# IO.net
KiCad netlist of a schematic drawn in Altium Designer
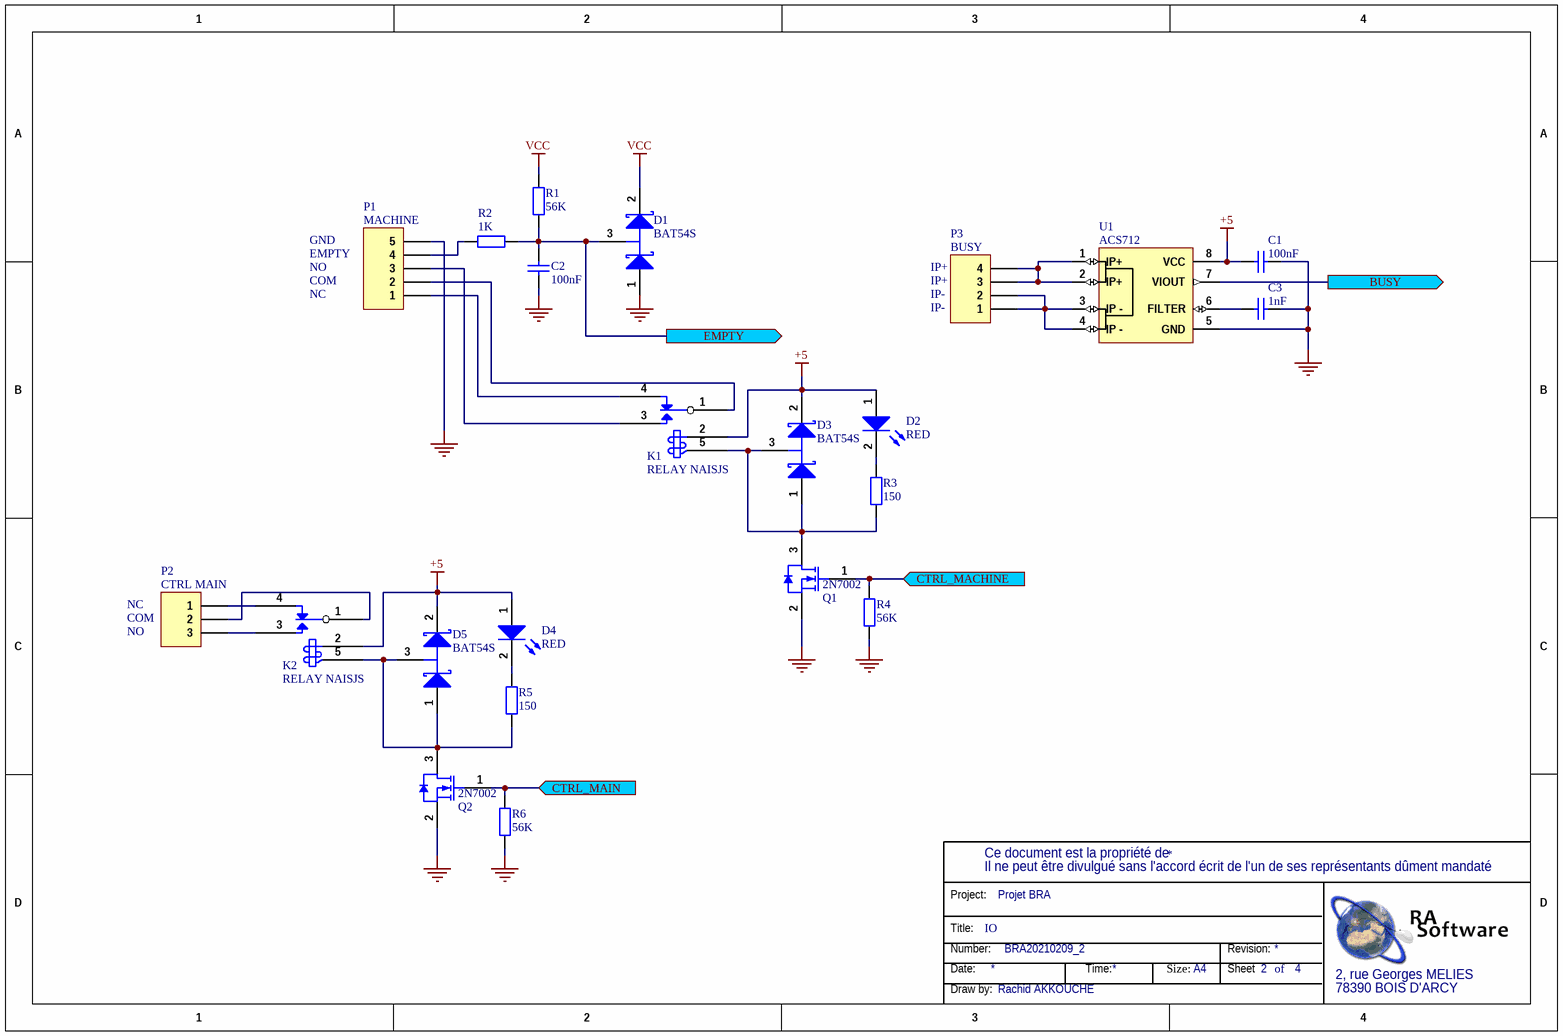
[diagram p0: IO.SchDoc]

(export (version "E")
  (design (tool "Eeschema 10.0.6"))
  (components
    (comp (ref "C1")
      (value "100nF")
      (footprint "C 0805(2012)x0.65")
      (description "Capacitor")
      (fields
        (field (name "MANUFACTURER") "MULTICOMP")
        (field (name "MANUFACTURER PART NUMBER") "MCCA000296")
      )
      (libsource (lib "BRA") (part "Cap 0805 100nF"))
    )
    (comp (ref "C2")
      (value "100nF")
      (footprint "C 0805(2012)x0.65")
      (description "Capacitor")
      (fields
        (field (name "MANUFACTURER") "MULTICOMP")
        (field (name "MANUFACTURER PART NUMBER") "MCCA000296")
      )
      (libsource (lib "BRA") (part "Cap 0805 100nF"))
    )
    (comp (ref "C3")
      (value "1nF")
      (footprint "C 0805(2012)x0.65")
      (description "Capacitor")
      (fields
        (field (name "MANUFACTURER") "SAMSUNG")
        (field (name "MANUFACTURER PART NUMBER") "CL05B102KB5NNNC")
      )
      (libsource (lib "BRA") (part "Cap 0805 1nF"))
    )
    (comp (ref "D1")
      (value "BAT54S")
      (footprint "BRA:SOT23")
      (description "Schottky Barrier Double Diode")
      (fields (field (name "MANUFACTURER") "MULTICOMP"))
      (libsource (lib "BRA") (part "BAT54S"))
    )
    (comp (ref "D2")
      (value "RED")
      (footprint "0603-LEDR")
      (description "Surface Mount Chip LED, Red")
      (fields
        (field (name "MANUFACTURER") "AVAGO TECHNOLOGIES")
        (field (name "MANUFACTURER PART NUMBER") "HSMH-C190.")
        (field (name "LONGUEUR/HAUTEUR") "1.6")
      )
      (libsource (lib "BRA") (part "HSMH-C190"))
    )
    (comp (ref "D3")
      (value "BAT54S")
      (footprint "SOT23")
      (description "Schottky Barrier Double Diode")
      (fields (field (name "MANUFACTURER") "MULTICOMP"))
      (libsource (lib "Ares") (part "BAT54S"))
    )
    (comp (ref "D4")
      (value "RED")
      (footprint "0603-LEDR")
      (description "Surface Mount Chip LED, Red")
      (fields
        (field (name "MANUFACTURER") "AVAGO TECHNOLOGIES")
        (field (name "MANUFACTURER PART NUMBER") "HSMH-C190.")
        (field (name "LONGUEUR/HAUTEUR") "1.6")
      )
      (libsource (lib "BRA") (part "HSMH-C190"))
    )
    (comp (ref "D5")
      (value "BAT54S")
      (footprint "SOT23")
      (description "Schottky Barrier Double Diode")
      (fields (field (name "MANUFACTURER") "MULTICOMP"))
      (libsource (lib "Ares") (part "BAT54S"))
    )
    (comp (ref "K1")
      (value "RELAY NAISJS")
      (footprint "RELAIG5L")
      (fields
        (field (name "MANUFACTURER") "OMRON ELECTRONIC COMPONENTS")
        (field (name "MANUFACTURER PART NUMBER") "G5LA1A412DC")
        (field (name "HAUTEUR, DIMENSION EXTERNE") "15.8")
      )
      (libsource (lib "UTIL_Library") (part "RELAY NAISJS"))
    )
    (comp (ref "K2")
      (value "RELAY NAISJS")
      (footprint "RELAIG5L")
      (fields
        (field (name "MANUFACTURER") "OMRON ELECTRONIC COMPONENTS")
        (field (name "MANUFACTURER PART NUMBER") "G5LA1A412DC")
        (field (name "HAUTEUR, DIMENSION EXTERNE") "15.8")
      )
      (libsource (lib "UTIL_Library") (part "RELAY NAISJS"))
    )
    (comp (ref "P1")
      (value "MACHINE")
      (footprint "CO5P508-RIGHT")
      (description "Header, 5-Pin")
      (fields (field (name "PUBLISHER") "Altium Limited"))
      (libsource (lib "Miscellaneous Connectors") (part "Header 5"))
    )
    (comp (ref "P2")
      (value "CTRL MAIN")
      (footprint "CO3P508 - 2")
      (description "Header, 3-Pin")
      (fields (field (name "PUBLISHER") "Altium Limited"))
      (libsource (lib "Miscellaneous Connectors") (part "Header 3"))
    )
    (comp (ref "P3")
      (value "BUSY")
      (footprint "CO4P508")
      (description "Header, 4-Pin")
      (fields (field (name "PUBLISHER") "Altium Limited"))
      (libsource (lib "Miscellaneous Connectors") (part "Header 4"))
    )
    (comp (ref "Q1")
      (value "2N7002")
      (footprint "SOT23")
      (description "N-channel Enhancement Mode Field-effect Transistor")
      (fields (field (name "MANUFACTURER") "FAIRCHILD SEMICONDUCTOR"))
      (libsource (lib "BRA") (part "2N7002"))
    )
    (comp (ref "Q2")
      (value "2N7002")
      (footprint "SOT23")
      (description "N-channel Enhancement Mode Field-effect Transistor")
      (fields (field (name "MANUFACTURER") "FAIRCHILD SEMICONDUCTOR"))
      (libsource (lib "BRA") (part "2N7002"))
    )
    (comp (ref "R1")
      (value "56K")
      (footprint "R 0805(2012)")
      (description "Resistor SMD 0805 56K")
      (fields
        (field (name "MANUFACTURER") "MULTICOMP")
        (field (name "MANUFACTURER PART NUMBER") "MC0.1W08051%56KFR")
      )
      (libsource (lib "BRA") (part "Resistor 0805 56K"))
    )
    (comp (ref "R2")
      (value "1K")
      (footprint "R 0805(2012)")
      (description "Resistor SMD 0805 1K")
      (fields
        (field (name "MANUFACTURER") "MULTICOMP")
        (field (name "MANUFACTURER PART NUMBER") "MC0.1W08051%1KFR")
      )
      (libsource (lib "BRA") (part "Resistor 0805 1K"))
    )
    (comp (ref "R3")
      (value "150")
      (footprint "R 0805(2012)")
      (description "Resistor SMD 0805 150")
      (fields
        (field (name "MANUFACTURER") "YAGEO")
        (field (name "MANUFACTURER PART NUMBER") "RC0805JR-07150KL")
      )
      (libsource (lib "BRA") (part "Resistor 0805 150"))
    )
    (comp (ref "R4")
      (value "56K")
      (footprint "R 0805(2012)")
      (description "Resistor")
      (fields
        (field (name "MANUFACTURER") "MULTICOMP")
        (field (name "MANUFACTURER PART NUMBER") "MC0.1W08051%56KFR")
      )
      (libsource (lib "BRA") (part "Resistor 0805 56K"))
    )
    (comp (ref "R5")
      (value "150")
      (footprint "R 0805(2012)")
      (description "Resistor SMD 0805 150")
      (fields
        (field (name "MANUFACTURER") "YAGEO")
        (field (name "MANUFACTURER PART NUMBER") "RC0805JR-07150KL")
      )
      (libsource (lib "BRA") (part "Resistor 0805 150"))
    )
    (comp (ref "R6")
      (value "56K")
      (footprint "R 0805(2012)")
      (description "Resistor")
      (fields
        (field (name "MANUFACTURER") "MULTICOMP")
        (field (name "MANUFACTURER PART NUMBER") "MC0.1W08051%56KFR")
      )
      (libsource (lib "BRA") (part "Resistor 0805 56K"))
    )
    (comp (ref "U1")
      (value "ACS712")
      (footprint "SOIC8")
      (description "HALL EFFECT CURRENT SENSOR")
      (fields
        (field (name "MANUFACTURER") "ALLEGRO MICROSYSTEMS")
        (field (name "MANUFACTURER PART NUMBER") "ACS712ELCTR-20A-T")
      )
      (libsource (lib "BRA") (part "ACS712"))
    )
  )
  (nets
    (net (code "1") (name "+5") (class "Default")
      (node (ref "C1") (pin "2") (pinfunction "2_2") (pintype "passive"))
      (node (ref "D2") (pin "1") (pinfunction "A_1") (pintype "passive"))
      (node (ref "D3") (pin "2") (pinfunction "K_2") (pintype "passive"))
      (node (ref "D4") (pin "1") (pinfunction "A_1") (pintype "passive"))
      (node (ref "D5") (pin "2") (pinfunction "K_2") (pintype "passive"))
      (node (ref "K1") (pin "2") (pinfunction "COIL1_2") (pintype "passive"))
      (node (ref "K2") (pin "2") (pinfunction "COIL1_2") (pintype "passive"))
      (node (ref "U1") (pin "8") (pinfunction "VCC_8") (pintype "power_in"))
    )
    (net (code "2") (name "/BUSY") (class "Default")
      (node (ref "U1") (pin "7") (pinfunction "VIOUT_7") (pintype "output"))
    )
    (net (code "3") (name "/CTRL_MACHINE") (class "Default")
      (node (ref "Q1") (pin "1") (pinfunction "G_1") (pintype "passive"))
      (node (ref "R4") (pin "2") (pinfunction "2_2") (pintype "passive"))
    )
    (net (code "4") (name "/CTRL_MAIN") (class "Default")
      (node (ref "Q2") (pin "1") (pinfunction "G_1") (pintype "passive"))
      (node (ref "R6") (pin "2") (pinfunction "2_2") (pintype "passive"))
    )
    (net (code "5") (name "/EMPTY") (class "Default")
      (node (ref "C2") (pin "2") (pinfunction "2_2") (pintype "passive"))
      (node (ref "D1") (pin "3") (pinfunction "C_3") (pintype "passive"))
      (node (ref "R1") (pin "1") (pinfunction "1_1") (pintype "passive"))
      (node (ref "R2") (pin "1") (pinfunction "1_1") (pintype "passive"))
    )
    (net (code "6") (name "GND") (class "Default")
      (node (ref "C1") (pin "1") (pinfunction "1_1") (pintype "passive"))
      (node (ref "C2") (pin "1") (pinfunction "1_1") (pintype "passive"))
      (node (ref "C3") (pin "2") (pinfunction "2_2") (pintype "passive"))
      (node (ref "D1") (pin "1") (pinfunction "A_1") (pintype "passive"))
      (node (ref "P1") (pin "5") (pinfunction "5_5") (pintype "passive"))
      (node (ref "Q1") (pin "2") (pinfunction "S_2") (pintype "passive"))
      (node (ref "Q2") (pin "2") (pinfunction "S_2") (pintype "passive"))
      (node (ref "R4") (pin "1") (pinfunction "1_1") (pintype "passive"))
      (node (ref "R6") (pin "1") (pinfunction "1_1") (pintype "passive"))
      (node (ref "U1") (pin "5") (pinfunction "GND_5") (pintype "power_in"))
    )
    (net (code "7") (name "Net-(D2-K)") (class "Default")
      (node (ref "D2") (pin "2") (pinfunction "K_2") (pintype "passive"))
      (node (ref "R3") (pin "2") (pinfunction "2_2") (pintype "passive"))
    )
    (net (code "8") (name "Net-(D3-A)") (class "Default")
      (node (ref "D3") (pin "1") (pinfunction "A_1") (pintype "passive"))
      (node (ref "D3") (pin "3") (pinfunction "C_3") (pintype "passive"))
      (node (ref "K1") (pin "5") (pinfunction "COIL2_5") (pintype "passive"))
      (node (ref "Q1") (pin "3") (pinfunction "D_3") (pintype "passive"))
      (node (ref "R3") (pin "1") (pinfunction "1_1") (pintype "passive"))
    )
    (net (code "9") (name "Net-(D4-K)") (class "Default")
      (node (ref "D4") (pin "2") (pinfunction "K_2") (pintype "passive"))
      (node (ref "R5") (pin "2") (pinfunction "2_2") (pintype "passive"))
    )
    (net (code "10") (name "Net-(D5-A)") (class "Default")
      (node (ref "D5") (pin "1") (pinfunction "A_1") (pintype "passive"))
      (node (ref "D5") (pin "3") (pinfunction "C_3") (pintype "passive"))
      (node (ref "K2") (pin "5") (pinfunction "COIL2_5") (pintype "passive"))
      (node (ref "Q2") (pin "3") (pinfunction "D_3") (pintype "passive"))
      (node (ref "R5") (pin "1") (pinfunction "1_1") (pintype "passive"))
    )
    (net (code "11") (name "Net-(K1-COMMON)") (class "Default")
      (node (ref "K1") (pin "1") (pinfunction "COMMON_1") (pintype "passive"))
      (node (ref "P1") (pin "2") (pinfunction "2_2") (pintype "passive"))
    )
    (net (code "12") (name "Net-(K1-NC)") (class "Default")
      (node (ref "K1") (pin "4") (pinfunction "NC_4") (pintype "passive"))
      (node (ref "P1") (pin "1") (pinfunction "1_1") (pintype "passive"))
    )
    (net (code "13") (name "Net-(K1-NO)") (class "Default")
      (node (ref "K1") (pin "3") (pinfunction "NO_3") (pintype "passive"))
      (node (ref "P1") (pin "3") (pinfunction "3_3") (pintype "passive"))
    )
    (net (code "14") (name "Net-(K2-COMMON)") (class "Default")
      (node (ref "K2") (pin "1") (pinfunction "COMMON_1") (pintype "passive"))
      (node (ref "P2") (pin "2") (pinfunction "2_2") (pintype "passive"))
    )
    (net (code "15") (name "Net-(K2-NC)") (class "Default")
      (node (ref "K2") (pin "4") (pinfunction "NC_4") (pintype "passive"))
      (node (ref "P2") (pin "1") (pinfunction "1_1") (pintype "passive"))
    )
    (net (code "16") (name "Net-(K2-NO)") (class "Default")
      (node (ref "K2") (pin "3") (pinfunction "NO_3") (pintype "passive"))
      (node (ref "P2") (pin "3") (pinfunction "3_3") (pintype "passive"))
    )
    (net (code "17") (name "Net-(P1-Pad4)") (class "Default")
      (node (ref "P1") (pin "4") (pinfunction "4_4") (pintype "passive"))
      (node (ref "R2") (pin "2") (pinfunction "2_2") (pintype "passive"))
    )
    (net (code "18") (name "Net-(P3-Pad1)") (class "Default")
      (node (ref "P3") (pin "1") (pinfunction "1_1") (pintype "passive"))
      (node (ref "P3") (pin "2") (pinfunction "2_2") (pintype "passive"))
      (node (ref "U1") (pin "3") (pinfunction "IP_-_3") (pintype "bidirectional"))
      (node (ref "U1") (pin "4") (pinfunction "IP_-_4") (pintype "bidirectional"))
    )
    (net (code "19") (name "Net-(P3-Pad3)") (class "Default")
      (node (ref "P3") (pin "3") (pinfunction "3_3") (pintype "passive"))
      (node (ref "P3") (pin "4") (pinfunction "4_4") (pintype "passive"))
      (node (ref "U1") (pin "1") (pinfunction "IP+_1") (pintype "bidirectional"))
      (node (ref "U1") (pin "2") (pinfunction "IP+_2") (pintype "bidirectional"))
    )
    (net (code "20") (name "Net-(U1-FILTER)") (class "Default")
      (node (ref "C3") (pin "1") (pinfunction "1_1") (pintype "passive"))
      (node (ref "U1") (pin "6") (pinfunction "FILTER_6") (pintype "bidirectional"))
    )
    (net (code "21") (name "VCC") (class "Default")
      (node (ref "D1") (pin "2") (pinfunction "K_2") (pintype "passive"))
      (node (ref "R1") (pin "2") (pinfunction "2_2") (pintype "passive"))
    )
  )
)
